# servo_power.net
KiCad netlist of a schematic drawn in Altium Designer
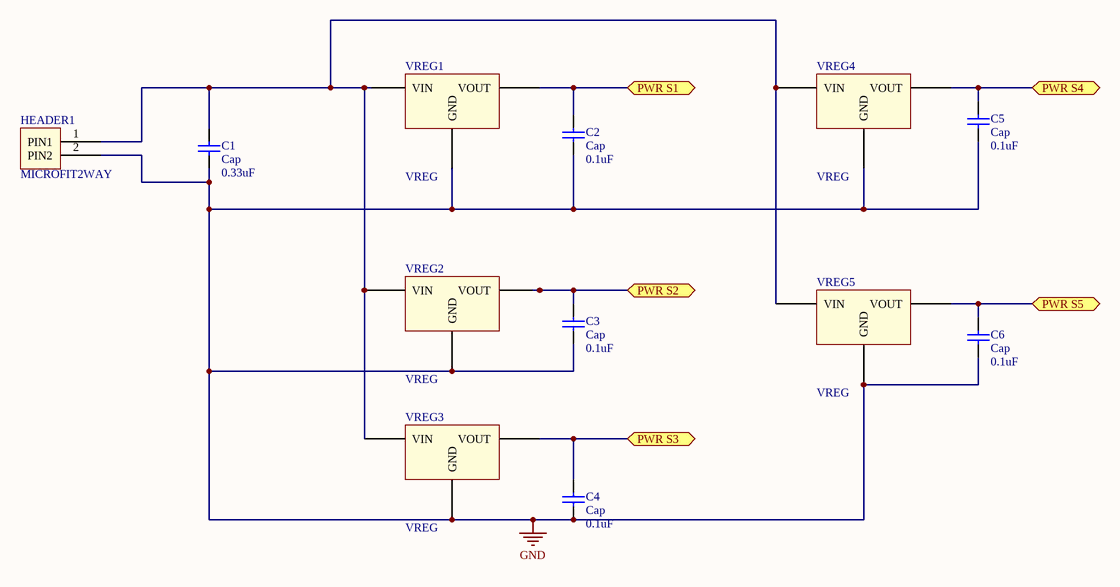
[diagram p0: servo_power.SchDoc]

(export (version "E")
  (design (tool "Eeschema 10.0.6"))
  (components
    (comp (ref "C1")
      (value "Cap")
      (footprint "RAD-0.3")
      (description "Capacitor")
      (fields (field (name "ALTIUM_VALUE") "0.33uF") (field (name "PUBLISHER") "Altium Limited"))
      (libsource (lib "Miscellaneous Devices") (part "Cap"))
    )
    (comp (ref "C2")
      (value "Cap")
      (footprint "RAD-0.3")
      (description "Capacitor")
      (fields (field (name "ALTIUM_VALUE") "0.1uF") (field (name "PUBLISHER") "Altium Limited"))
      (libsource (lib "Miscellaneous Devices") (part "Cap"))
    )
    (comp (ref "C3")
      (value "Cap")
      (footprint "RAD-0.3")
      (description "Capacitor")
      (fields (field (name "ALTIUM_VALUE") "0.1uF") (field (name "PUBLISHER") "Altium Limited"))
      (libsource (lib "Miscellaneous Devices") (part "Cap"))
    )
    (comp (ref "C4")
      (value "Cap")
      (footprint "RAD-0.3")
      (description "Capacitor")
      (fields (field (name "ALTIUM_VALUE") "0.1uF") (field (name "PUBLISHER") "Altium Limited"))
      (libsource (lib "Miscellaneous Devices") (part "Cap"))
    )
    (comp (ref "C5")
      (value "Cap")
      (footprint "RAD-0.3")
      (description "Capacitor")
      (fields (field (name "ALTIUM_VALUE") "0.1uF") (field (name "PUBLISHER") "Altium Limited"))
      (libsource (lib "Miscellaneous Devices") (part "Cap"))
    )
    (comp (ref "C6")
      (value "Cap")
      (footprint "RAD-0.3")
      (description "Capacitor")
      (fields (field (name "ALTIUM_VALUE") "0.1uF") (field (name "PUBLISHER") "Altium Limited"))
      (libsource (lib "Miscellaneous Devices") (part "Cap"))
    )
    (comp (ref "HEADER1")
      (value "MICROFIT2WAY")
      (footprint "MICROFIT2WAY")
      (description "MICROFIT2WAY HEADER")
      (libsource (lib "MICROFIT_2WAY") (part "MICROFIT2WAY HEADER"))
    )
    (comp (ref "VREG1")
      (value "VREG")
      (footprint "TO-220 VREG")
      (description "VOLTAGE REGULATOR")
      (libsource (lib "VREG") (part "VOLTAGE REGULATOR"))
    )
    (comp (ref "VREG2")
      (value "VREG")
      (footprint "TO-220 VREG")
      (description "VOLTAGE REGULATOR")
      (libsource (lib "VREG") (part "VOLTAGE REGULATOR"))
    )
    (comp (ref "VREG3")
      (value "VREG")
      (footprint "TO-220 VREG")
      (description "VOLTAGE REGULATOR")
      (libsource (lib "VREG") (part "VOLTAGE REGULATOR"))
    )
    (comp (ref "VREG4")
      (value "VREG")
      (footprint "TO-220 VREG")
      (description "VOLTAGE REGULATOR")
      (libsource (lib "VREG") (part "VOLTAGE REGULATOR"))
    )
    (comp (ref "VREG5")
      (value "VREG")
      (footprint "TO-220 VREG")
      (description "VOLTAGE REGULATOR")
      (libsource (lib "VREG") (part "VOLTAGE REGULATOR"))
    )
  )
  (nets
    (net (code "1") (name "/PWR S1") (class "Default")
      (node (ref "C2") (pin "2") (pinfunction "2_2") (pintype "passive"))
      (node (ref "VREG1") (pin "3") (pinfunction "VOUT_3") (pintype "passive"))
    )
    (net (code "2") (name "/PWR S2") (class "Default")
      (node (ref "C3") (pin "2") (pinfunction "2_2") (pintype "passive"))
      (node (ref "VREG2") (pin "3") (pinfunction "VOUT_3") (pintype "passive"))
    )
    (net (code "3") (name "/PWR S3") (class "Default")
      (node (ref "C4") (pin "2") (pinfunction "2_2") (pintype "passive"))
      (node (ref "VREG3") (pin "3") (pinfunction "VOUT_3") (pintype "passive"))
    )
    (net (code "4") (name "/PWR S4") (class "Default")
      (node (ref "C5") (pin "2") (pinfunction "2_2") (pintype "passive"))
      (node (ref "VREG4") (pin "3") (pinfunction "VOUT_3") (pintype "passive"))
    )
    (net (code "5") (name "/PWR S5") (class "Default")
      (node (ref "C6") (pin "2") (pinfunction "2_2") (pintype "passive"))
      (node (ref "VREG5") (pin "3") (pinfunction "VOUT_3") (pintype "passive"))
    )
    (net (code "6") (name "GND") (class "Default")
      (node (ref "C1") (pin "1") (pinfunction "1_1") (pintype "passive"))
      (node (ref "C2") (pin "1") (pinfunction "1_1") (pintype "passive"))
      (node (ref "C3") (pin "1") (pinfunction "1_1") (pintype "passive"))
      (node (ref "C4") (pin "1") (pinfunction "1_1") (pintype "passive"))
      (node (ref "C5") (pin "1") (pinfunction "1_1") (pintype "passive"))
      (node (ref "C6") (pin "1") (pinfunction "1_1") (pintype "passive"))
      (node (ref "HEADER1") (pin "2") (pinfunction "PIN2_2") (pintype "passive"))
      (node (ref "VREG1") (pin "2") (pinfunction "GND_2") (pintype "passive"))
      (node (ref "VREG2") (pin "2") (pinfunction "GND_2") (pintype "passive"))
      (node (ref "VREG3") (pin "2") (pinfunction "GND_2") (pintype "passive"))
      (node (ref "VREG4") (pin "2") (pinfunction "GND_2") (pintype "passive"))
      (node (ref "VREG5") (pin "2") (pinfunction "GND_2") (pintype "passive"))
    )
    (net (code "7") (name "Net-(HEADER1-PIN1)") (class "Default")
      (node (ref "C1") (pin "2") (pinfunction "2_2") (pintype "passive"))
      (node (ref "HEADER1") (pin "1") (pinfunction "PIN1_1") (pintype "passive"))
      (node (ref "VREG1") (pin "1") (pinfunction "VIN_1") (pintype "passive"))
      (node (ref "VREG2") (pin "1") (pinfunction "VIN_1") (pintype "passive"))
      (node (ref "VREG3") (pin "1") (pinfunction "VIN_1") (pintype "passive"))
      (node (ref "VREG4") (pin "1") (pinfunction "VIN_1") (pintype "passive"))
      (node (ref "VREG5") (pin "1") (pinfunction "VIN_1") (pintype "passive"))
    )
  )
)
